# LowPassFilter.net
KiCad netlist of a schematic drawn in Altium Designer
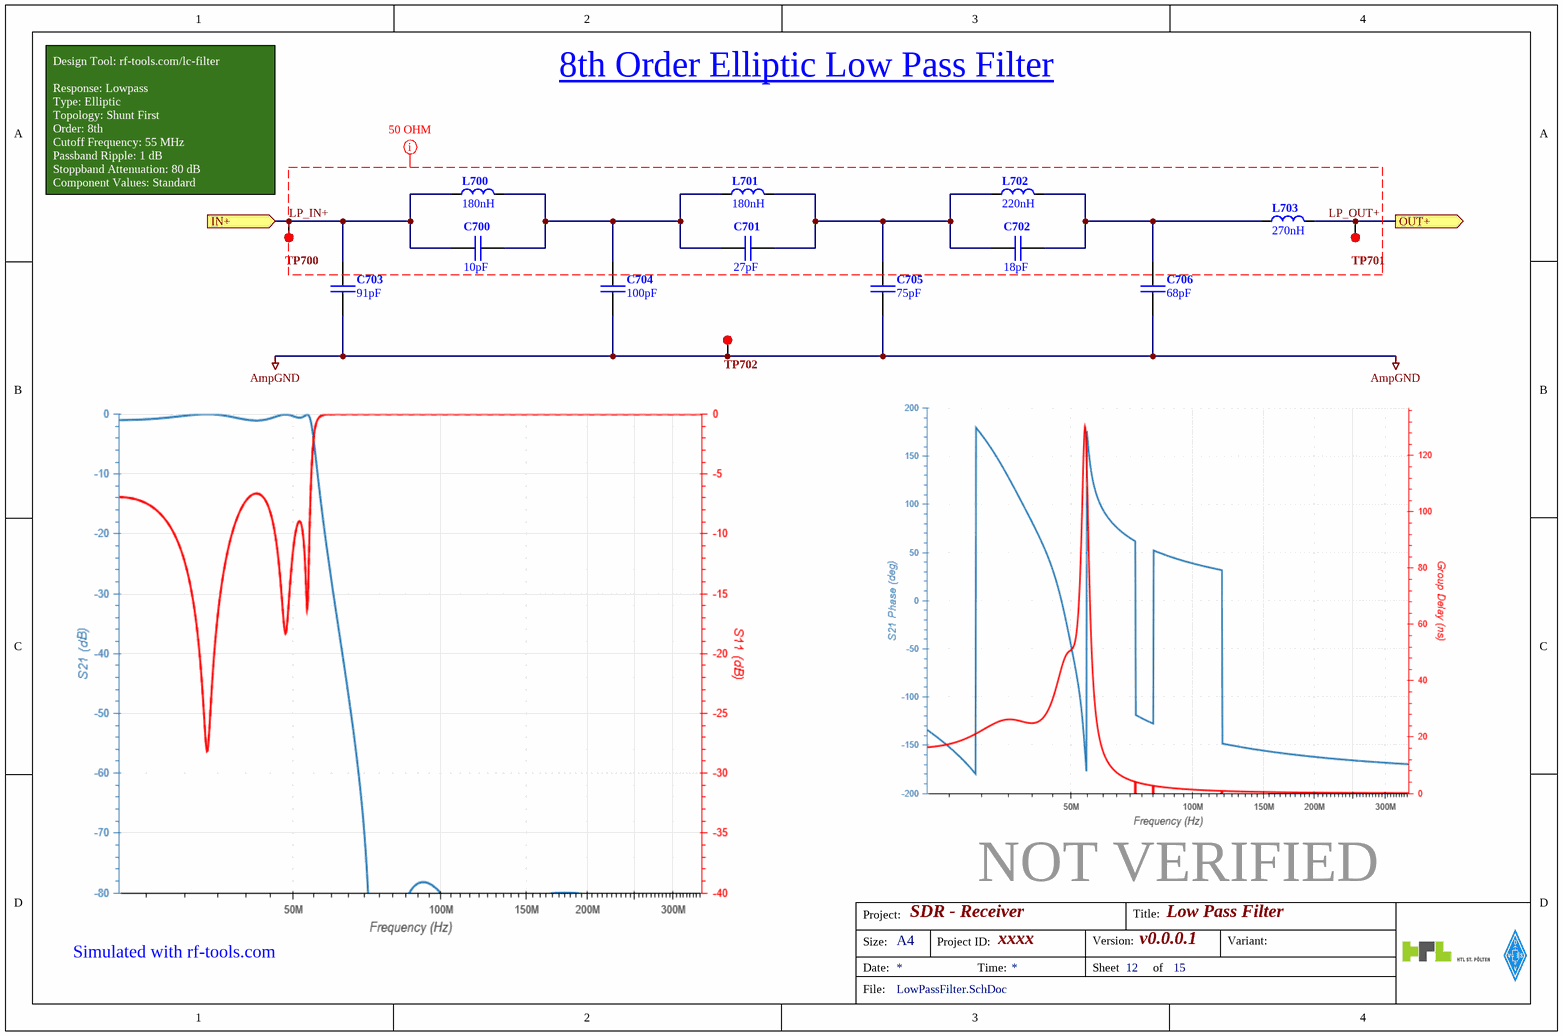
[diagram p0: LowPassFilter.SchDoc]

(export (version "E")
  (design (tool "Eeschema 10.0.6"))
  (components
    (comp (ref "C700")
      (value "10pF")
      (footprint "PrometheusLib:C_0603_N [CAPC1608N IPC]")
      (libsource (lib "PrometheusLib") (part "C_GENERIC"))
    )
    (comp (ref "C701")
      (value "27pF")
      (footprint "PrometheusLib:C_0603_N [CAPC1608N IPC]")
      (libsource (lib "PrometheusLib") (part "C_GENERIC"))
    )
    (comp (ref "C702")
      (value "18pF")
      (footprint "PrometheusLib:C_0603_N [CAPC1608N IPC]")
      (libsource (lib "PrometheusLib") (part "C_GENERIC"))
    )
    (comp (ref "C703")
      (value "91pF")
      (footprint "PrometheusLib:C_0603_N [CAPC1608N IPC]")
      (libsource (lib "PrometheusLib") (part "C_GENERIC"))
    )
    (comp (ref "C704")
      (value "100pF")
      (footprint "PrometheusLib:C_0603_N [CAPC1608N IPC]")
      (libsource (lib "PrometheusLib") (part "C_GENERIC"))
    )
    (comp (ref "C705")
      (value "75pF")
      (footprint "PrometheusLib:C_0603_N [CAPC1608N IPC]")
      (libsource (lib "PrometheusLib") (part "C_GENERIC"))
    )
    (comp (ref "C706")
      (value "68pF")
      (footprint "PrometheusLib:C_0603_N [CAPC1608N IPC]")
      (libsource (lib "PrometheusLib") (part "C_GENERIC"))
    )
    (comp (ref "L700")
      (value "180nH")
      (footprint "PrometheusLib:L_0603_N [INDC1608N IPC]")
      (fields (field (name "PROMETHEUS_MANPARTNO") "744761218C"))
      (libsource (lib "PrometheusLib") (part "L_GENERIC"))
    )
    (comp (ref "L701")
      (value "180nH")
      (footprint "PrometheusLib:L_0603_N [INDC1608N IPC]")
      (fields (field (name "PROMETHEUS_MANPARTNO") "744761218C"))
      (libsource (lib "PrometheusLib") (part "L_GENERIC"))
    )
    (comp (ref "L702")
      (value "220nH")
      (footprint "PrometheusLib:L_0603_N [INDC1608N IPC]")
      (fields (field (name "PROMETHEUS_MANPARTNO") "744761222C"))
      (libsource (lib "PrometheusLib") (part "L_GENERIC"))
    )
    (comp (ref "L703")
      (value "270nH")
      (footprint "PrometheusLib:L_0603_N [INDC1608N IPC]")
      (fields (field (name "PROMETHEUS_MANPARTNO") "744761227C"))
      (libsource (lib "PrometheusLib") (part "L_GENERIC"))
    )
    (comp (ref "TP700")
      (value "TP_GENERIC")
      (footprint "PrometheusLib:TP_0.8_P100T")
      (description "Needle Test Point")
      (libsource (lib "PrometheusLib") (part "TP_GENERIC"))
    )
    (comp (ref "TP701")
      (value "TP_GENERIC")
      (footprint "PrometheusLib:TP_0.8_P100T")
      (description "Needle Test Point")
      (libsource (lib "PrometheusLib") (part "TP_GENERIC"))
    )
    (comp (ref "TP702")
      (value "TP_GENERIC")
      (footprint "PrometheusLib:TP_0.8_P100T")
      (description "Needle Test Point")
      (libsource (lib "PrometheusLib") (part "TP_GENERIC"))
    )
  )
  (nets
    (net (code "1") (name "/LP_IN+") (class "Default")
      (node (ref "C700") (pin "1") (pintype "passive"))
      (node (ref "C703") (pin "2") (pintype "passive"))
      (node (ref "L700") (pin "1") (pinfunction "1_1") (pintype "passive"))
      (node (ref "TP700") (pin "1") (pinfunction "1_1") (pintype "passive"))
    )
    (net (code "2") (name "/LP_OUT+") (class "Default")
      (node (ref "L703") (pin "2") (pinfunction "2_2") (pintype "passive"))
      (node (ref "TP701") (pin "1") (pinfunction "1_1") (pintype "passive"))
    )
    (net (code "3") (name "AmpGND") (class "Default")
      (node (ref "C703") (pin "1") (pintype "passive"))
      (node (ref "C704") (pin "1") (pintype "passive"))
      (node (ref "C705") (pin "1") (pintype "passive"))
      (node (ref "C706") (pin "1") (pintype "passive"))
      (node (ref "TP702") (pin "1") (pinfunction "1_1") (pintype "passive"))
    )
    (net (code "4") (name "Net-(C700-Pad2)") (class "Default")
      (node (ref "C700") (pin "2") (pintype "passive"))
      (node (ref "C701") (pin "1") (pintype "passive"))
      (node (ref "C704") (pin "2") (pintype "passive"))
      (node (ref "L700") (pin "2") (pinfunction "2_2") (pintype "passive"))
      (node (ref "L701") (pin "1") (pinfunction "1_1") (pintype "passive"))
    )
    (net (code "5") (name "Net-(C701-Pad2)") (class "Default")
      (node (ref "C701") (pin "2") (pintype "passive"))
      (node (ref "C702") (pin "1") (pintype "passive"))
      (node (ref "C705") (pin "2") (pintype "passive"))
      (node (ref "L701") (pin "2") (pinfunction "2_2") (pintype "passive"))
      (node (ref "L702") (pin "1") (pinfunction "1_1") (pintype "passive"))
    )
    (net (code "6") (name "Net-(C702-Pad2)") (class "Default")
      (node (ref "C702") (pin "2") (pintype "passive"))
      (node (ref "C706") (pin "2") (pintype "passive"))
      (node (ref "L702") (pin "2") (pinfunction "2_2") (pintype "passive"))
      (node (ref "L703") (pin "1") (pinfunction "1_1") (pintype "passive"))
    )
  )
)
